# guante_izquierdo.net
KiCad netlist of a schematic drawn in EAGLE
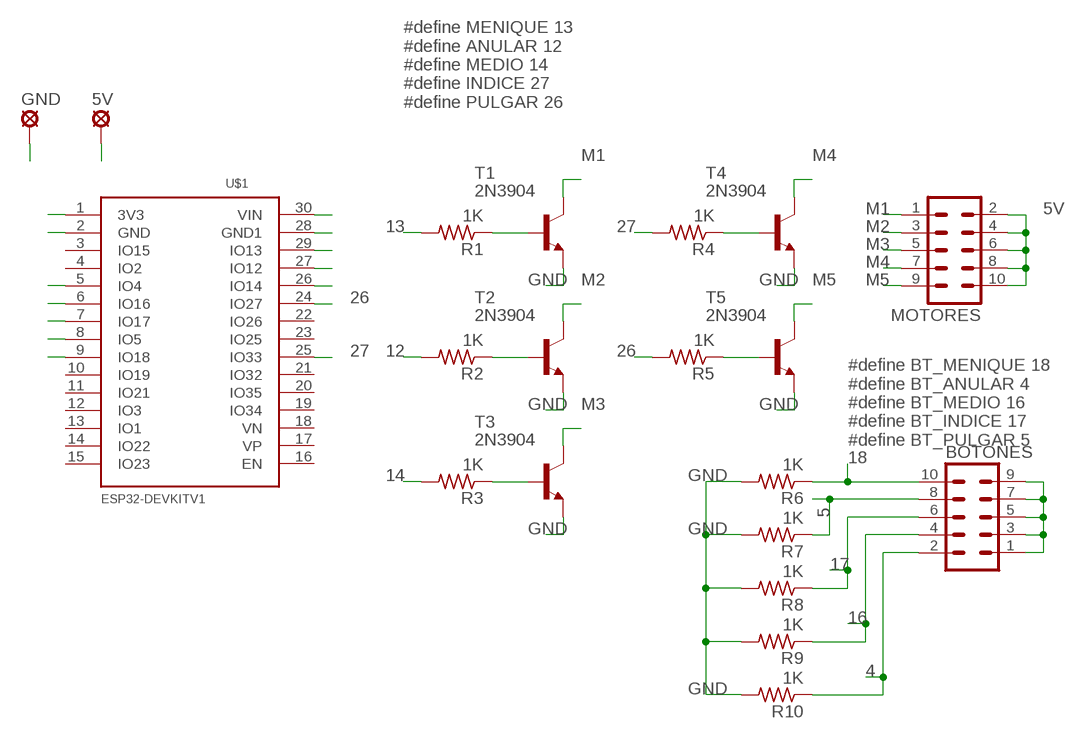
[diagram p0: schematic, sheet 1]

(export (version "E")
  (design (tool "Eeschema 10.0.6"))
  (components
    (comp (ref "5V")
      (value "MCS10B")
      (footprint "eagle-import:MCS10B")
      (libsource (lib "eagle-import") (part "MCS10B"))
    )
    (comp (ref "BOTONES")
      (value "MA05-2")
      (footprint "eagle-import:MA05-2")
      (libsource (lib "eagle-import") (part "MA05-2"))
    )
    (comp (ref "GND")
      (value "MCS10B")
      (footprint "eagle-import:MCS10B")
      (libsource (lib "eagle-import") (part "MCS10B"))
    )
    (comp (ref "MOTORES")
      (value "MA05-2")
      (footprint "eagle-import:MA05-2")
      (libsource (lib "eagle-import") (part "MA05-2"))
    )
    (comp (ref "R1")
      (value "1K")
      (footprint "eagle-import:0207_10")
      (libsource (lib "eagle-import") (part "R-US_0207/10"))
    )
    (comp (ref "R2")
      (value "1K")
      (footprint "eagle-import:0207_10")
      (libsource (lib "eagle-import") (part "R-US_0207/10"))
    )
    (comp (ref "R3")
      (value "1K")
      (footprint "eagle-import:0207_10")
      (libsource (lib "eagle-import") (part "R-US_0207/10"))
    )
    (comp (ref "R4")
      (value "1K")
      (footprint "eagle-import:0207_10")
      (libsource (lib "eagle-import") (part "R-US_0207/10"))
    )
    (comp (ref "R5")
      (value "1K")
      (footprint "eagle-import:0207_10")
      (libsource (lib "eagle-import") (part "R-US_0207/10"))
    )
    (comp (ref "R6")
      (value "1K")
      (footprint "eagle-import:0207_10")
      (libsource (lib "eagle-import") (part "R-US_0207/10"))
    )
    (comp (ref "R7")
      (value "1K")
      (footprint "eagle-import:0207_10")
      (libsource (lib "eagle-import") (part "R-US_0207/10"))
    )
    (comp (ref "R8")
      (value "1K")
      (footprint "eagle-import:0207_10")
      (libsource (lib "eagle-import") (part "R-US_0207/10"))
    )
    (comp (ref "R9")
      (value "1K")
      (footprint "eagle-import:0207_10")
      (libsource (lib "eagle-import") (part "R-US_0207/10"))
    )
    (comp (ref "R10")
      (value "1K")
      (footprint "eagle-import:0207_10")
      (libsource (lib "eagle-import") (part "R-US_0207/10"))
    )
    (comp (ref "T1")
      (value "2N3904")
      (footprint "eagle-import:TO92-EBC")
      (libsource (lib "eagle-import") (part "-NPN-TO92-EBC"))
    )
    (comp (ref "T2")
      (value "2N3904")
      (footprint "eagle-import:TO92-EBC")
      (libsource (lib "eagle-import") (part "-NPN-TO92-EBC"))
    )
    (comp (ref "T3")
      (value "2N3904")
      (footprint "eagle-import:TO92-EBC")
      (libsource (lib "eagle-import") (part "-NPN-TO92-EBC"))
    )
    (comp (ref "T4")
      (value "2N3904")
      (footprint "eagle-import:TO92-EBC")
      (libsource (lib "eagle-import") (part "-NPN-TO92-EBC"))
    )
    (comp (ref "T5")
      (value "2N3904")
      (footprint "eagle-import:TO92-EBC")
      (libsource (lib "eagle-import") (part "-NPN-TO92-EBC"))
    )
    (comp (ref "U$1")
      (value "ESP32DEVKITV1")
      (footprint "eagle-import:ESP32-DEVKITV1")
      (libsource (lib "eagle-import") (part "ESP32DEVKITV1"))
    )
  )
  (nets
    (net (code "1") (name "/3V3") (class "Default")
      (node (ref "BOTONES") (pin "1") (pinfunction "1_1") (pintype "passive"))
      (node (ref "BOTONES") (pin "3") (pinfunction "3_3") (pintype "passive"))
      (node (ref "BOTONES") (pin "5") (pinfunction "5_5") (pintype "passive"))
      (node (ref "BOTONES") (pin "7") (pinfunction "7_7") (pintype "passive"))
      (node (ref "BOTONES") (pin "9") (pinfunction "9_9") (pintype "passive"))
      (node (ref "U$1") (pin "1") (pinfunction "3V3_1") (pintype "bidirectional"))
    )
    (net (code "2") (name "/4") (class "Default")
      (node (ref "BOTONES") (pin "2") (pinfunction "2_2") (pintype "passive"))
      (node (ref "R10") (pin "1") (pinfunction "1_1") (pintype "passive"))
      (node (ref "U$1") (pin "5") (pinfunction "IO4_5") (pintype "bidirectional"))
    )
    (net (code "3") (name "/5") (class "Default")
      (node (ref "BOTONES") (pin "8") (pinfunction "8_8") (pintype "passive"))
      (node (ref "R7") (pin "1") (pinfunction "1_1") (pintype "passive"))
      (node (ref "U$1") (pin "8") (pinfunction "IO5_8") (pintype "bidirectional"))
    )
    (net (code "4") (name "/5V") (class "Default")
      (node (ref "5V") (pin "MP") (pinfunction "MP_MP") (pintype "passive"))
      (node (ref "MOTORES") (pin "10") (pinfunction "10_10") (pintype "passive"))
      (node (ref "MOTORES") (pin "2") (pinfunction "2_2") (pintype "passive"))
      (node (ref "MOTORES") (pin "4") (pinfunction "4_4") (pintype "passive"))
      (node (ref "MOTORES") (pin "6") (pinfunction "6_6") (pintype "passive"))
      (node (ref "MOTORES") (pin "8") (pinfunction "8_8") (pintype "passive"))
      (node (ref "U$1") (pin "30") (pinfunction "VIN_30") (pintype "bidirectional"))
    )
    (net (code "5") (name "/12") (class "Default")
      (node (ref "R2") (pin "2") (pinfunction "2_2") (pintype "passive"))
      (node (ref "U$1") (pin "27") (pinfunction "IO12_27") (pintype "bidirectional"))
    )
    (net (code "6") (name "/13") (class "Default")
      (node (ref "R1") (pin "2") (pinfunction "2_2") (pintype "passive"))
      (node (ref "U$1") (pin "29") (pinfunction "IO13_29") (pintype "bidirectional"))
    )
    (net (code "7") (name "/14") (class "Default")
      (node (ref "R3") (pin "2") (pinfunction "2_2") (pintype "passive"))
      (node (ref "U$1") (pin "26") (pinfunction "IO14_26") (pintype "bidirectional"))
    )
    (net (code "8") (name "/16") (class "Default")
      (node (ref "BOTONES") (pin "4") (pinfunction "4_4") (pintype "passive"))
      (node (ref "R9") (pin "1") (pinfunction "1_1") (pintype "passive"))
      (node (ref "U$1") (pin "6") (pinfunction "IO16_6") (pintype "bidirectional"))
    )
    (net (code "9") (name "/17") (class "Default")
      (node (ref "BOTONES") (pin "6") (pinfunction "6_6") (pintype "passive"))
      (node (ref "R8") (pin "1") (pinfunction "1_1") (pintype "passive"))
      (node (ref "U$1") (pin "7") (pinfunction "IO17_7") (pintype "bidirectional"))
    )
    (net (code "10") (name "/18") (class "Default")
      (node (ref "BOTONES") (pin "10") (pinfunction "10_10") (pintype "passive"))
      (node (ref "R6") (pin "1") (pinfunction "1_1") (pintype "passive"))
      (node (ref "U$1") (pin "9") (pinfunction "IO18_9") (pintype "bidirectional"))
    )
    (net (code "11") (name "/26") (class "Default")
      (node (ref "R5") (pin "2") (pinfunction "2_2") (pintype "passive"))
      (node (ref "U$1") (pin "24") (pinfunction "IO27_24") (pintype "bidirectional"))
    )
    (net (code "12") (name "/27") (class "Default")
      (node (ref "R4") (pin "2") (pinfunction "2_2") (pintype "passive"))
      (node (ref "U$1") (pin "25") (pinfunction "IO33_25") (pintype "bidirectional"))
    )
    (net (code "13") (name "/GND") (class "Default")
      (node (ref "GND") (pin "MP") (pinfunction "MP_MP") (pintype "passive"))
      (node (ref "R10") (pin "2") (pinfunction "2_2") (pintype "passive"))
      (node (ref "R6") (pin "2") (pinfunction "2_2") (pintype "passive"))
      (node (ref "R7") (pin "2") (pinfunction "2_2") (pintype "passive"))
      (node (ref "R8") (pin "2") (pinfunction "2_2") (pintype "passive"))
      (node (ref "R9") (pin "2") (pinfunction "2_2") (pintype "passive"))
      (node (ref "T1") (pin "E") (pinfunction "E_E") (pintype "passive"))
      (node (ref "T2") (pin "E") (pinfunction "E_E") (pintype "passive"))
      (node (ref "T3") (pin "E") (pinfunction "E_E") (pintype "passive"))
      (node (ref "T4") (pin "E") (pinfunction "E_E") (pintype "passive"))
      (node (ref "T5") (pin "E") (pinfunction "E_E") (pintype "passive"))
      (node (ref "U$1") (pin "2") (pinfunction "GND_2") (pintype "bidirectional"))
      (node (ref "U$1") (pin "28") (pinfunction "GND1_28") (pintype "bidirectional"))
    )
    (net (code "14") (name "/M1") (class "Default")
      (node (ref "MOTORES") (pin "1") (pinfunction "1_1") (pintype "passive"))
      (node (ref "T1") (pin "C") (pinfunction "C_C") (pintype "passive"))
    )
    (net (code "15") (name "/M2") (class "Default")
      (node (ref "MOTORES") (pin "3") (pinfunction "3_3") (pintype "passive"))
      (node (ref "T2") (pin "C") (pinfunction "C_C") (pintype "passive"))
    )
    (net (code "16") (name "/M3") (class "Default")
      (node (ref "MOTORES") (pin "5") (pinfunction "5_5") (pintype "passive"))
      (node (ref "T3") (pin "C") (pinfunction "C_C") (pintype "passive"))
    )
    (net (code "17") (name "/M4") (class "Default")
      (node (ref "MOTORES") (pin "7") (pinfunction "7_7") (pintype "passive"))
      (node (ref "T4") (pin "C") (pinfunction "C_C") (pintype "passive"))
    )
    (net (code "18") (name "/M5") (class "Default")
      (node (ref "MOTORES") (pin "9") (pinfunction "9_9") (pintype "passive"))
      (node (ref "T5") (pin "C") (pinfunction "C_C") (pintype "passive"))
    )
    (net (code "19") (name "Net-(R1-Pad1)") (class "Default")
      (node (ref "R1") (pin "1") (pinfunction "1_1") (pintype "passive"))
      (node (ref "T1") (pin "B") (pinfunction "B_B") (pintype "passive"))
    )
    (net (code "20") (name "Net-(R2-Pad1)") (class "Default")
      (node (ref "R2") (pin "1") (pinfunction "1_1") (pintype "passive"))
      (node (ref "T2") (pin "B") (pinfunction "B_B") (pintype "passive"))
    )
    (net (code "21") (name "Net-(R3-Pad1)") (class "Default")
      (node (ref "R3") (pin "1") (pinfunction "1_1") (pintype "passive"))
      (node (ref "T3") (pin "B") (pinfunction "B_B") (pintype "passive"))
    )
    (net (code "22") (name "Net-(R4-Pad1)") (class "Default")
      (node (ref "R4") (pin "1") (pinfunction "1_1") (pintype "passive"))
      (node (ref "T4") (pin "B") (pinfunction "B_B") (pintype "passive"))
    )
    (net (code "23") (name "Net-(R5-Pad1)") (class "Default")
      (node (ref "R5") (pin "1") (pinfunction "1_1") (pintype "passive"))
      (node (ref "T5") (pin "B") (pinfunction "B_B") (pintype "passive"))
    )
    (net (code "24") (name "unconnected-(U$1-EN-Pad16)") (class "Default")
      (node (ref "U$1") (pin "16") (pinfunction "EN_16") (pintype "bidirectional"))
    )
    (net (code "25") (name "unconnected-(U$1-IO1-Pad13)") (class "Default")
      (node (ref "U$1") (pin "13") (pinfunction "IO1_13") (pintype "bidirectional"))
    )
    (net (code "26") (name "unconnected-(U$1-IO2-Pad4)") (class "Default")
      (node (ref "U$1") (pin "4") (pinfunction "IO2_4") (pintype "bidirectional"))
    )
    (net (code "27") (name "unconnected-(U$1-IO3-Pad12)") (class "Default")
      (node (ref "U$1") (pin "12") (pinfunction "IO3_12") (pintype "bidirectional"))
    )
    (net (code "28") (name "unconnected-(U$1-IO15-Pad3)") (class "Default")
      (node (ref "U$1") (pin "3") (pinfunction "IO15_3") (pintype "bidirectional"))
    )
    (net (code "29") (name "unconnected-(U$1-IO19-Pad10)") (class "Default")
      (node (ref "U$1") (pin "10") (pinfunction "IO19_10") (pintype "bidirectional"))
    )
    (net (code "30") (name "unconnected-(U$1-IO21-Pad11)") (class "Default")
      (node (ref "U$1") (pin "11") (pinfunction "IO21_11") (pintype "bidirectional"))
    )
    (net (code "31") (name "unconnected-(U$1-IO22-Pad14)") (class "Default")
      (node (ref "U$1") (pin "14") (pinfunction "IO22_14") (pintype "bidirectional"))
    )
    (net (code "32") (name "unconnected-(U$1-IO23-Pad15)") (class "Default")
      (node (ref "U$1") (pin "15") (pinfunction "IO23_15") (pintype "bidirectional"))
    )
    (net (code "33") (name "unconnected-(U$1-IO25-Pad23)") (class "Default")
      (node (ref "U$1") (pin "23") (pinfunction "IO25_23") (pintype "bidirectional"))
    )
    (net (code "34") (name "unconnected-(U$1-IO26-Pad22)") (class "Default")
      (node (ref "U$1") (pin "22") (pinfunction "IO26_22") (pintype "bidirectional"))
    )
    (net (code "35") (name "unconnected-(U$1-IO32-Pad21)") (class "Default")
      (node (ref "U$1") (pin "21") (pinfunction "IO32_21") (pintype "bidirectional"))
    )
    (net (code "36") (name "unconnected-(U$1-IO34-Pad19)") (class "Default")
      (node (ref "U$1") (pin "19") (pinfunction "IO34_19") (pintype "bidirectional"))
    )
    (net (code "37") (name "unconnected-(U$1-IO35-Pad20)") (class "Default")
      (node (ref "U$1") (pin "20") (pinfunction "IO35_20") (pintype "bidirectional"))
    )
    (net (code "38") (name "unconnected-(U$1-VN-Pad18)") (class "Default")
      (node (ref "U$1") (pin "18") (pinfunction "VN_18") (pintype "bidirectional"))
    )
    (net (code "39") (name "unconnected-(U$1-VP-Pad17)") (class "Default")
      (node (ref "U$1") (pin "17") (pinfunction "VP_17") (pintype "bidirectional"))
    )
  )
)
